# usb_levalaszto_v1.net
KiCad netlist of a schematic drawn in EAGLE
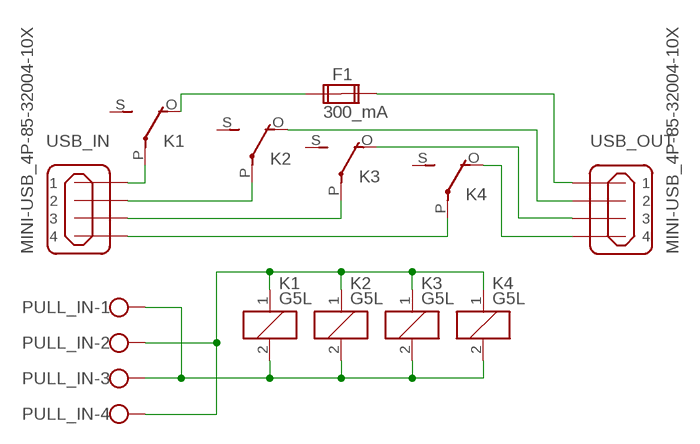
[diagram p0: schematic, sheet 1]

(export (version "E")
  (design (tool "Eeschema 10.0.6"))
  (components
    (comp (ref "F1")
      (value "300_mA")
      (footprint "eagle-import:FUSE1")
      (libsource (lib "eagle-import") (part "FUSE2P"))
    )
    (comp (ref "K1")
      (value "G5L")
      (footprint "eagle-import:G5LE")
      (libsource (lib "eagle-import") (part "G5L"))
    )
    (comp (ref "K2")
      (value "G5L")
      (footprint "eagle-import:G5LE")
      (libsource (lib "eagle-import") (part "G5L"))
    )
    (comp (ref "K3")
      (value "G5L")
      (footprint "eagle-import:G5LE")
      (libsource (lib "eagle-import") (part "G5L"))
    )
    (comp (ref "K4")
      (value "G5L")
      (footprint "eagle-import:G5LE")
      (libsource (lib "eagle-import") (part "G5L"))
    )
    (comp (ref "PULL_IN")
      (value "W237-4")
      (footprint "eagle-import:W237-4")
      (libsource (lib "eagle-import") (part "W237-4"))
    )
    (comp (ref "USB_IN")
      (value "MINI-USB_4P-85-32004-10X")
      (footprint "eagle-import:85-32004-10X")
      (libsource (lib "eagle-import") (part "MINI-USB_4P-85-32004-10X"))
    )
    (comp (ref "USB_OUT")
      (value "MINI-USB_4P-85-32004-10X")
      (footprint "eagle-import:85-32004-10X")
      (libsource (lib "eagle-import") (part "MINI-USB_4P-85-32004-10X"))
    )
  )
  (nets
    (net (code "1") (name "Net-(F1-Pad1A)") (class "Default")
      (node (ref "F1") (pin "1A") (pinfunction "1A_1A") (pintype "passive"))
      (node (ref "K1") (pin "O") (pinfunction "O_O") (pintype "passive"))
    )
    (net (code "2") (name "Net-(F1-Pad2A)") (class "Default")
      (node (ref "F1") (pin "2A") (pinfunction "2A_2A") (pintype "passive"))
      (node (ref "USB_OUT") (pin "1") (pinfunction "1_1") (pintype "passive"))
    )
    (net (code "3") (name "Net-(K1-PadP)") (class "Default")
      (node (ref "K1") (pin "P") (pinfunction "P_P") (pintype "passive"))
      (node (ref "USB_IN") (pin "1") (pinfunction "1_1") (pintype "passive"))
    )
    (net (code "4") (name "Net-(K2-PadO)") (class "Default")
      (node (ref "K2") (pin "O") (pinfunction "O_O") (pintype "passive"))
      (node (ref "USB_OUT") (pin "2") (pinfunction "2_2") (pintype "passive"))
    )
    (net (code "5") (name "Net-(K2-PadP)") (class "Default")
      (node (ref "K2") (pin "P") (pinfunction "P_P") (pintype "passive"))
      (node (ref "USB_IN") (pin "2") (pinfunction "2_2") (pintype "passive"))
    )
    (net (code "6") (name "Net-(K3-PadO)") (class "Default")
      (node (ref "K3") (pin "O") (pinfunction "O_O") (pintype "passive"))
      (node (ref "USB_OUT") (pin "3") (pinfunction "3_3") (pintype "passive"))
    )
    (net (code "7") (name "Net-(K3-PadP)") (class "Default")
      (node (ref "K3") (pin "P") (pinfunction "P_P") (pintype "passive"))
      (node (ref "USB_IN") (pin "3") (pinfunction "3_3") (pintype "passive"))
    )
    (net (code "8") (name "Net-(K4-PadO)") (class "Default")
      (node (ref "K4") (pin "O") (pinfunction "O_O") (pintype "passive"))
      (node (ref "USB_OUT") (pin "4") (pinfunction "4_4") (pintype "passive"))
    )
    (net (code "9") (name "Net-(K4-PadP)") (class "Default")
      (node (ref "K4") (pin "P") (pinfunction "P_P") (pintype "passive"))
      (node (ref "USB_IN") (pin "4") (pinfunction "4_4") (pintype "passive"))
    )
    (net (code "10") (name "Net-(PULL_INA-KL)") (class "Default")
      (node (ref "K1") (pin "2") (pinfunction "2_2") (pintype "passive"))
      (node (ref "K2") (pin "2") (pinfunction "2_2") (pintype "passive"))
      (node (ref "K3") (pin "2") (pinfunction "2_2") (pintype "passive"))
      (node (ref "K4") (pin "2") (pinfunction "2_2") (pintype "passive"))
      (node (ref "PULL_IN") (pin "1") (pinfunction "KL_1") (pintype "passive"))
      (node (ref "PULL_IN") (pin "3") (pinfunction "KL_3") (pintype "passive"))
    )
    (net (code "11") (name "Net-(PULL_INB-KL)") (class "Default")
      (node (ref "K1") (pin "1") (pinfunction "1_1") (pintype "passive"))
      (node (ref "K2") (pin "1") (pinfunction "1_1") (pintype "passive"))
      (node (ref "K3") (pin "1") (pinfunction "1_1") (pintype "passive"))
      (node (ref "K4") (pin "1") (pinfunction "1_1") (pintype "passive"))
      (node (ref "PULL_IN") (pin "2") (pinfunction "KL_2") (pintype "passive"))
      (node (ref "PULL_IN") (pin "4") (pinfunction "KL_4") (pintype "passive"))
    )
    (net (code "12") (name "unconnected-(F1-Pad1B)") (class "Default")
      (node (ref "F1") (pin "1B") (pinfunction "1B_1B") (pintype "passive"))
    )
    (net (code "13") (name "unconnected-(F1-Pad2B)") (class "Default")
      (node (ref "F1") (pin "2B") (pinfunction "2B_2B") (pintype "passive"))
    )
    (net (code "14") (name "unconnected-(K1-PadS)") (class "Default")
      (node (ref "K1") (pin "S") (pinfunction "S_S") (pintype "passive"))
    )
    (net (code "15") (name "unconnected-(K2-PadS)") (class "Default")
      (node (ref "K2") (pin "S") (pinfunction "S_S") (pintype "passive"))
    )
    (net (code "16") (name "unconnected-(K3-PadS)") (class "Default")
      (node (ref "K3") (pin "S") (pinfunction "S_S") (pintype "passive"))
    )
    (net (code "17") (name "unconnected-(K4-PadS)") (class "Default")
      (node (ref "K4") (pin "S") (pinfunction "S_S") (pintype "passive"))
    )
  )
)
